# bmsMaster_can.net
KiCad netlist of a schematic drawn in Altium Designer
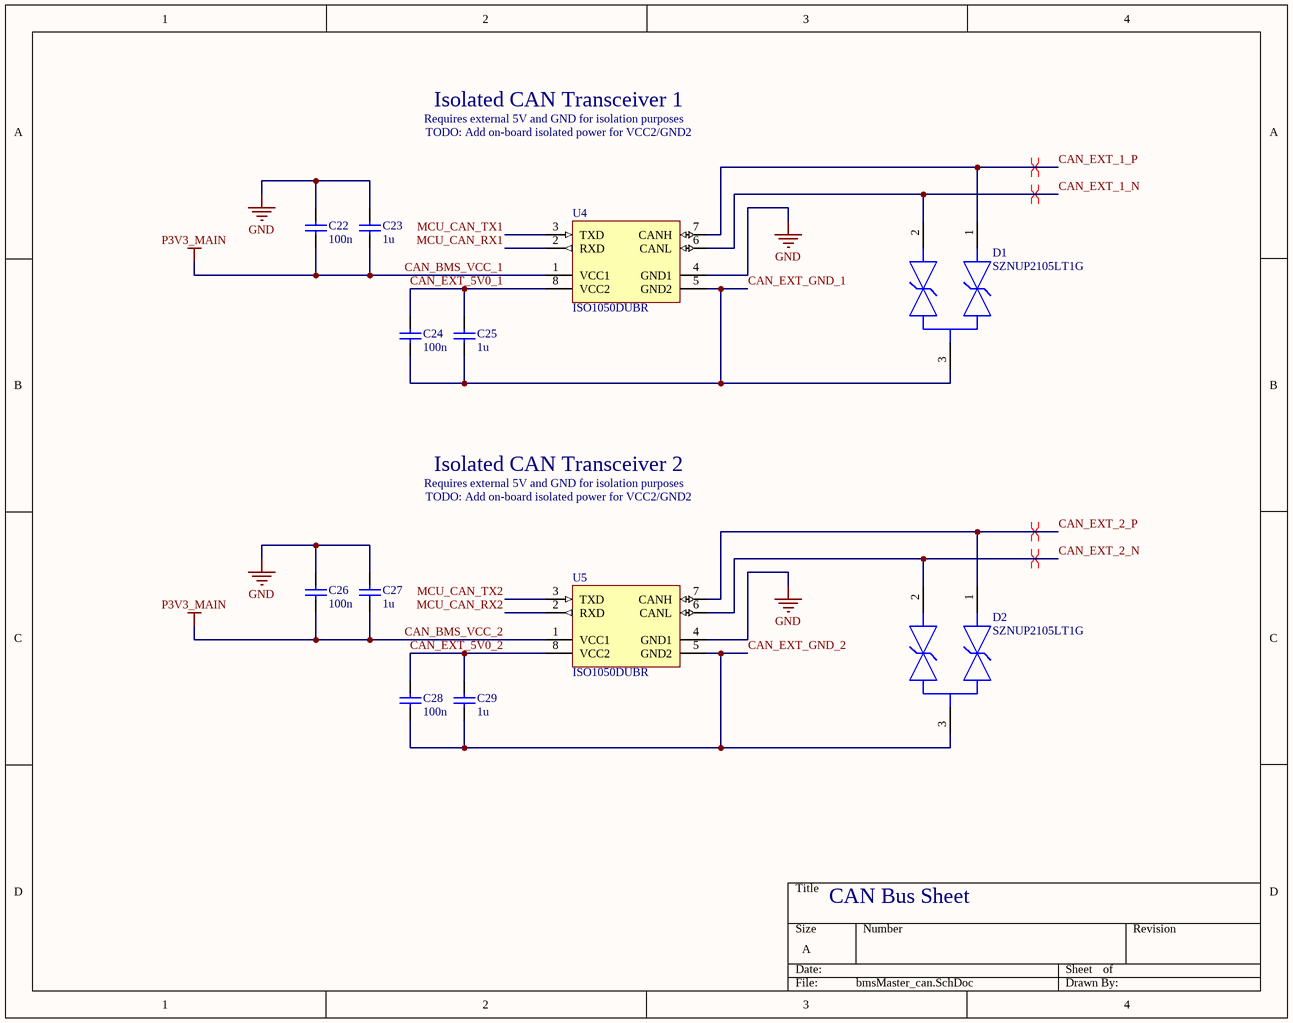
[diagram p0: bmsMaster_can.SchDoc]

(export (version "E")
  (design (tool "Eeschema 10.0.6"))
  (components
    (comp (ref "C22")
      (value "100n")
      (description "Capacitor")
      (libsource (lib "Simulation Generic Components") (part "Capacitor"))
    )
    (comp (ref "C23")
      (value "1u")
      (description "Capacitor")
      (libsource (lib "Simulation Generic Components") (part "Capacitor"))
    )
    (comp (ref "C24")
      (value "100n")
      (description "Capacitor")
      (libsource (lib "Simulation Generic Components") (part "Capacitor"))
    )
    (comp (ref "C25")
      (value "1u")
      (description "Capacitor")
      (libsource (lib "Simulation Generic Components") (part "Capacitor"))
    )
    (comp (ref "C26")
      (value "100n")
      (description "Capacitor")
      (libsource (lib "Simulation Generic Components") (part "Capacitor"))
    )
    (comp (ref "C27")
      (value "1u")
      (description "Capacitor")
      (libsource (lib "Simulation Generic Components") (part "Capacitor"))
    )
    (comp (ref "C28")
      (value "100n")
      (description "Capacitor")
      (libsource (lib "Simulation Generic Components") (part "Capacitor"))
    )
    (comp (ref "C29")
      (value "1u")
      (description "Capacitor")
      (libsource (lib "Simulation Generic Components") (part "Capacitor"))
    )
    (comp (ref "D1")
      (value "SZNUP2105LT1G")
      (footprint "FP-318-08-MFG")
      (description "TVS DIODE 24V 44V SOT23-3")
      (fields
        (field (name "OCTOPART") "https://octopart.com/sznup2105lt1g-on+semiconductor-22134626")
        (field (name "MANUFACTURER") "ON Semiconductor")
      )
      (libsource (lib "Altium Content Vault") (part "9fadcfe560bc2ec8fec8016e4fb2740"))
    )
    (comp (ref "D2")
      (value "SZNUP2105LT1G")
      (footprint "FP-318-08-MFG")
      (description "TVS DIODE 24V 44V SOT23-3")
      (fields
        (field (name "OCTOPART") "https://octopart.com/sznup2105lt1g-on+semiconductor-22134626")
        (field (name "MANUFACTURER") "ON Semiconductor")
      )
      (libsource (lib "Altium Content Vault") (part "9fadcfe560bc2ec8fec8016e4fb2740"))
    )
    (comp (ref "U4")
      (value "ISO1050DUBR")
      (footprint "DUB0008A_L")
      (description "Isolated CAN Transceiver, -55 to 105 degC, 8-pin SOP (DUB), Green (RoHS & no Sb/Br)")
      (fields (field (name "MANUFACTURER") "Texas Instruments"))
      (libsource (lib "Altium Content Vault") (part "TI-ISO1050-SOP_DUB-8"))
    )
    (comp (ref "U5")
      (value "ISO1050DUBR")
      (footprint "DUB0008A_L")
      (description "Isolated CAN Transceiver, -55 to 105 degC, 8-pin SOP (DUB), Green (RoHS & no Sb/Br)")
      (fields (field (name "MANUFACTURER") "Texas Instruments"))
      (libsource (lib "Altium Content Vault") (part "TI-ISO1050-SOP_DUB-8"))
    )
  )
  (nets
    (net (code "1") (name "/CAN_EXT_1_N") (class "Default")
      (node (ref "D1") (pin "2") (pinfunction "2_2") (pintype "passive"))
      (node (ref "U4") (pin "6") (pinfunction "CANL_6") (pintype "bidirectional"))
    )
    (net (code "2") (name "/CAN_EXT_1_P") (class "Default")
      (node (ref "D1") (pin "1") (pinfunction "1_1") (pintype "passive"))
      (node (ref "U4") (pin "7") (pinfunction "CANH_7") (pintype "bidirectional"))
    )
    (net (code "3") (name "/CAN_EXT_2_N") (class "Default")
      (node (ref "D2") (pin "2") (pinfunction "2_2") (pintype "passive"))
      (node (ref "U5") (pin "6") (pinfunction "CANL_6") (pintype "bidirectional"))
    )
    (net (code "4") (name "/CAN_EXT_2_P") (class "Default")
      (node (ref "D2") (pin "1") (pinfunction "1_1") (pintype "passive"))
      (node (ref "U5") (pin "7") (pinfunction "CANH_7") (pintype "bidirectional"))
    )
    (net (code "5") (name "/CAN_EXT_5V0_1") (class "Default")
      (node (ref "C24") (pin "2") (pinfunction "2_2") (pintype "passive"))
      (node (ref "C25") (pin "2") (pinfunction "2_2") (pintype "passive"))
      (node (ref "U4") (pin "8") (pinfunction "VCC2_8") (pintype "power_in"))
    )
    (net (code "6") (name "/CAN_EXT_5V0_2") (class "Default")
      (node (ref "C28") (pin "2") (pinfunction "2_2") (pintype "passive"))
      (node (ref "C29") (pin "2") (pinfunction "2_2") (pintype "passive"))
      (node (ref "U5") (pin "8") (pinfunction "VCC2_8") (pintype "power_in"))
    )
    (net (code "7") (name "/CAN_EXT_GND_1") (class "Default")
      (node (ref "C24") (pin "1") (pinfunction "1_1") (pintype "passive"))
      (node (ref "C25") (pin "1") (pinfunction "1_1") (pintype "passive"))
      (node (ref "D1") (pin "3") (pinfunction "3_3") (pintype "passive"))
      (node (ref "U4") (pin "5") (pinfunction "GND2_5") (pintype "power_in"))
    )
    (net (code "8") (name "/CAN_EXT_GND_2") (class "Default")
      (node (ref "C28") (pin "1") (pinfunction "1_1") (pintype "passive"))
      (node (ref "C29") (pin "1") (pinfunction "1_1") (pintype "passive"))
      (node (ref "D2") (pin "3") (pinfunction "3_3") (pintype "passive"))
      (node (ref "U5") (pin "5") (pinfunction "GND2_5") (pintype "power_in"))
    )
    (net (code "9") (name "/MCU_CAN_RX1") (class "Default")
      (node (ref "U4") (pin "2") (pinfunction "RXD_2") (pintype "output"))
    )
    (net (code "10") (name "/MCU_CAN_RX2") (class "Default")
      (node (ref "U5") (pin "2") (pinfunction "RXD_2") (pintype "output"))
    )
    (net (code "11") (name "/MCU_CAN_TX1") (class "Default")
      (node (ref "U4") (pin "3") (pinfunction "TXD_3") (pintype "input"))
    )
    (net (code "12") (name "/MCU_CAN_TX2") (class "Default")
      (node (ref "U5") (pin "3") (pinfunction "TXD_3") (pintype "input"))
    )
    (net (code "13") (name "GND") (class "Default")
      (node (ref "C22") (pin "2") (pinfunction "2_2") (pintype "passive"))
      (node (ref "C23") (pin "2") (pinfunction "2_2") (pintype "passive"))
      (node (ref "C26") (pin "2") (pinfunction "2_2") (pintype "passive"))
      (node (ref "C27") (pin "2") (pinfunction "2_2") (pintype "passive"))
      (node (ref "U4") (pin "4") (pinfunction "GND1_4") (pintype "power_in"))
      (node (ref "U5") (pin "4") (pinfunction "GND1_4") (pintype "power_in"))
    )
    (net (code "14") (name "P3V3_MAIN") (class "Default")
      (node (ref "C22") (pin "1") (pinfunction "1_1") (pintype "passive"))
      (node (ref "C23") (pin "1") (pinfunction "1_1") (pintype "passive"))
      (node (ref "C26") (pin "1") (pinfunction "1_1") (pintype "passive"))
      (node (ref "C27") (pin "1") (pinfunction "1_1") (pintype "passive"))
      (node (ref "U4") (pin "1") (pinfunction "VCC1_1") (pintype "power_in"))
      (node (ref "U5") (pin "1") (pinfunction "VCC1_1") (pintype "power_in"))
    )
  )
)
